# ProPrj_CraftVia-MakerCard-S-v1-Rev0_2026.net
KiCad netlist of a schematic drawn in EasyEDA Pro
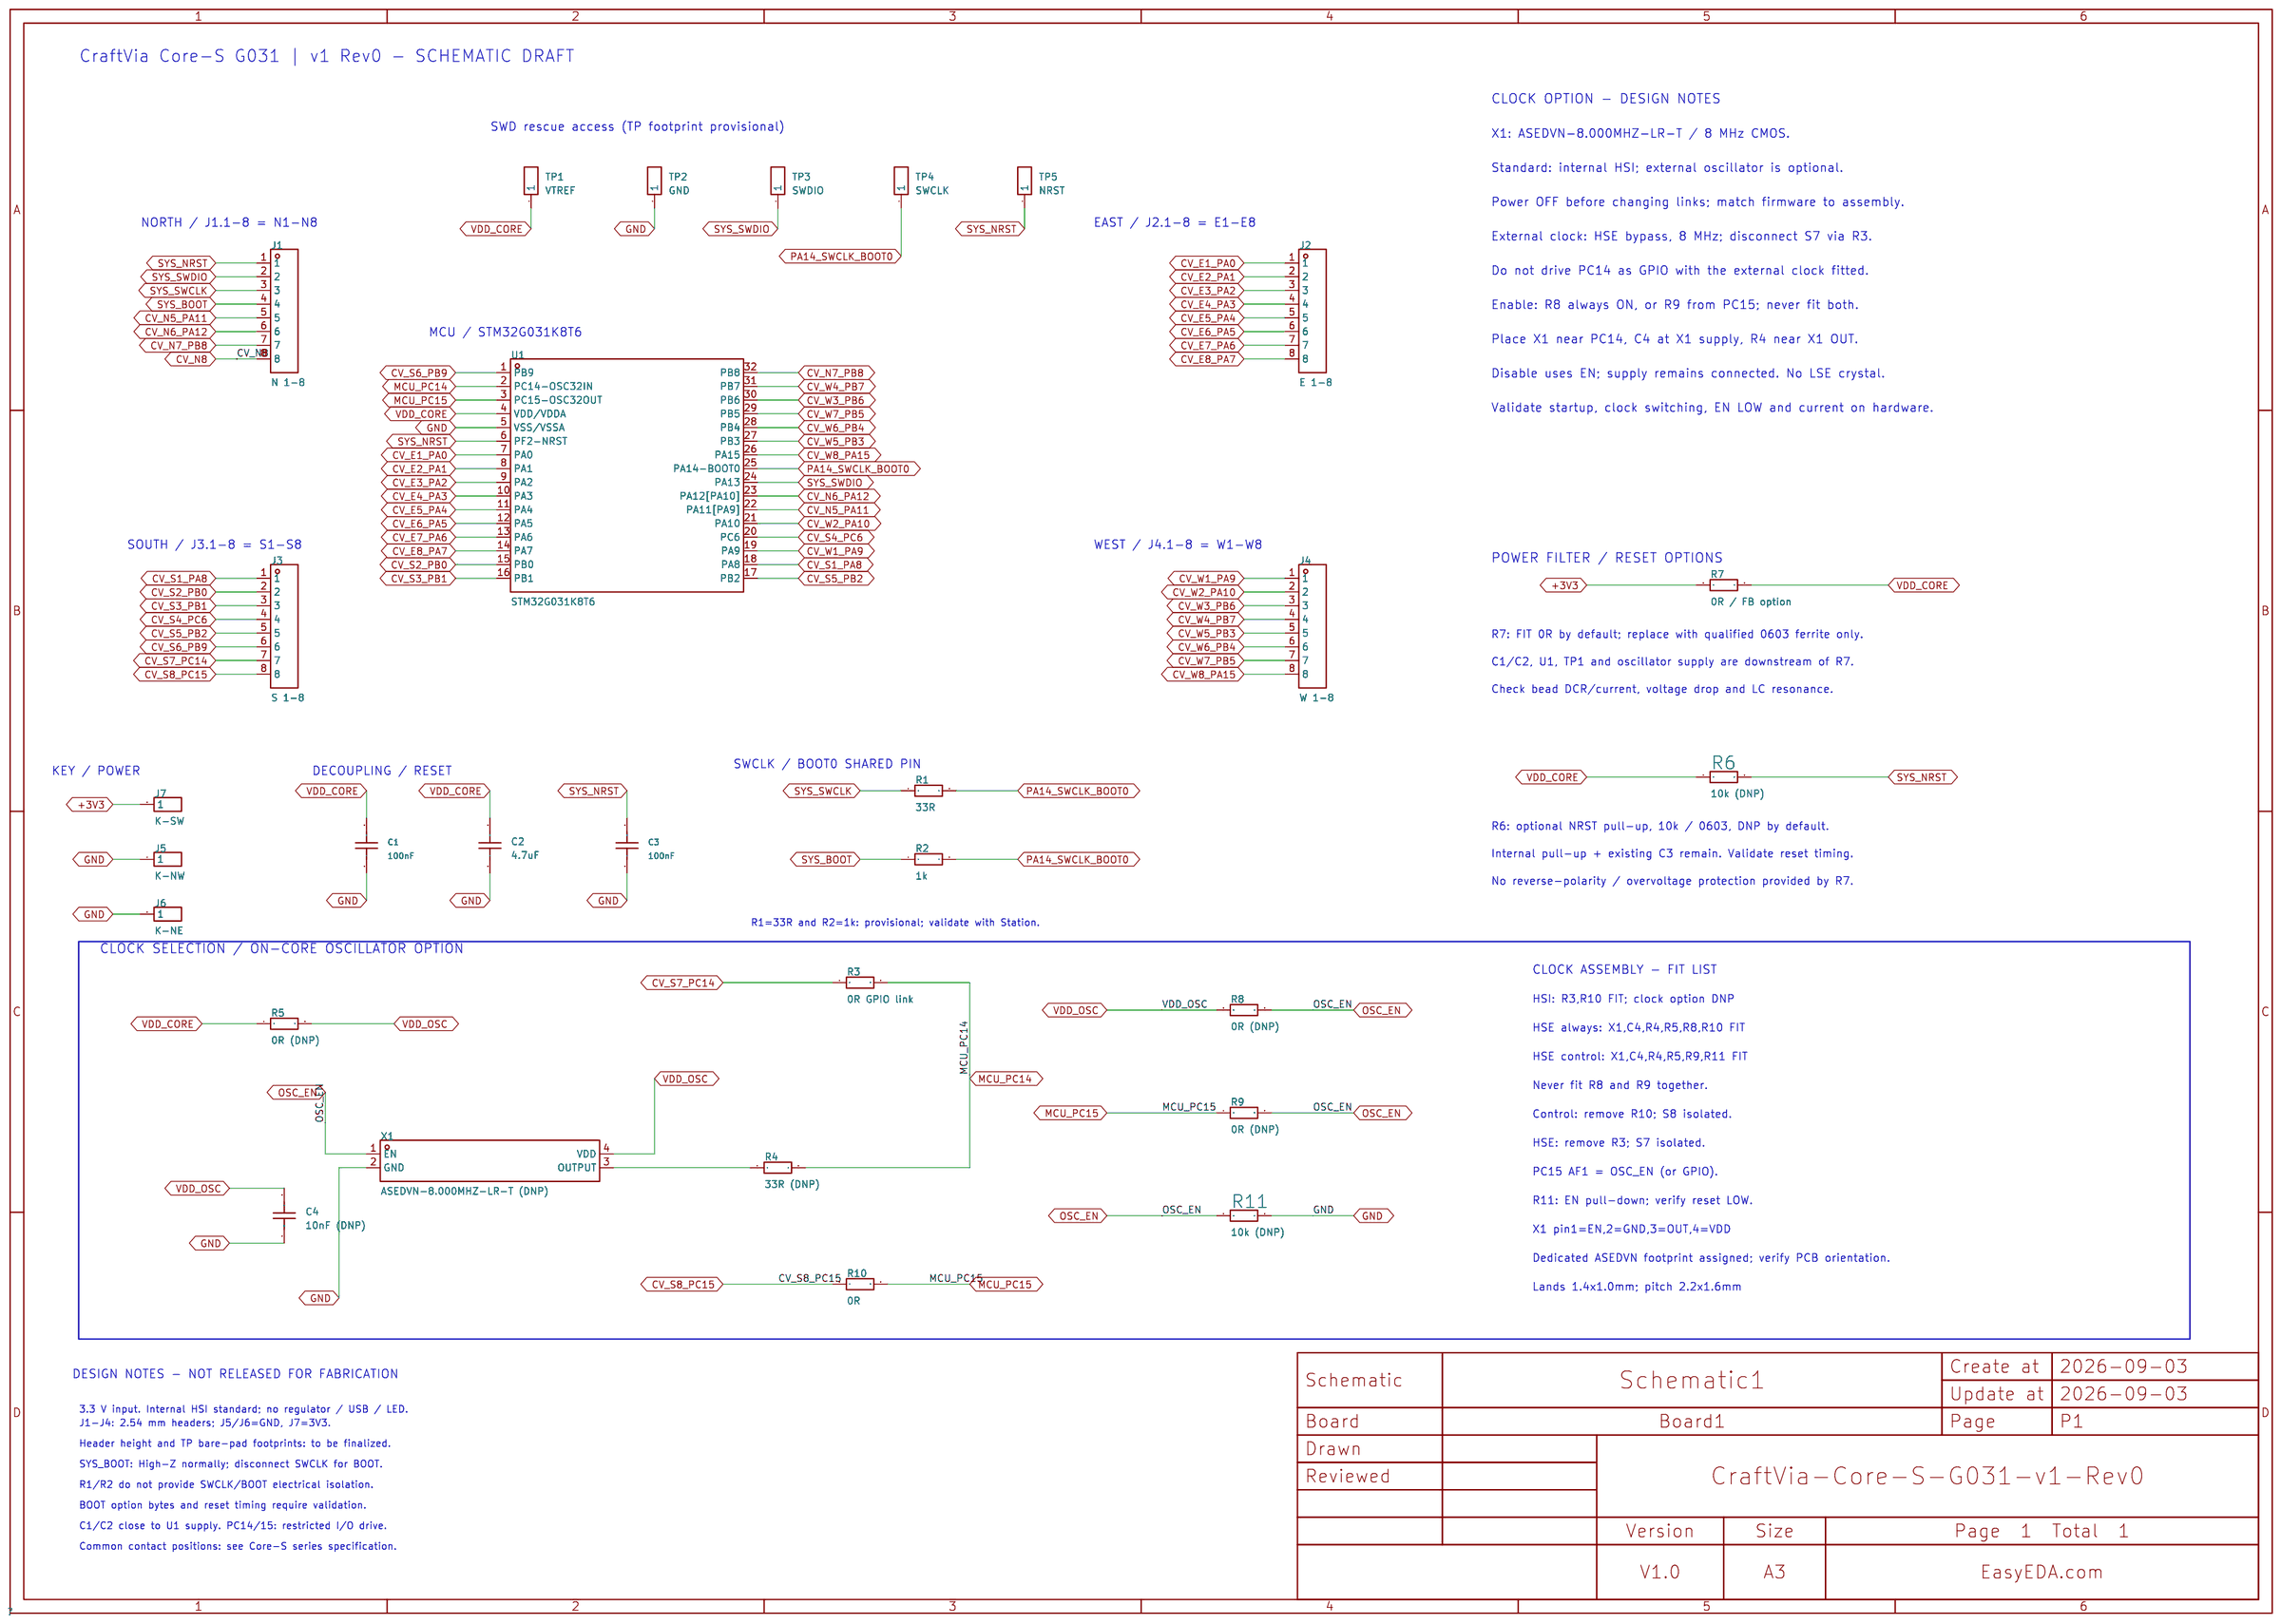
[diagram p0: Core-G031]
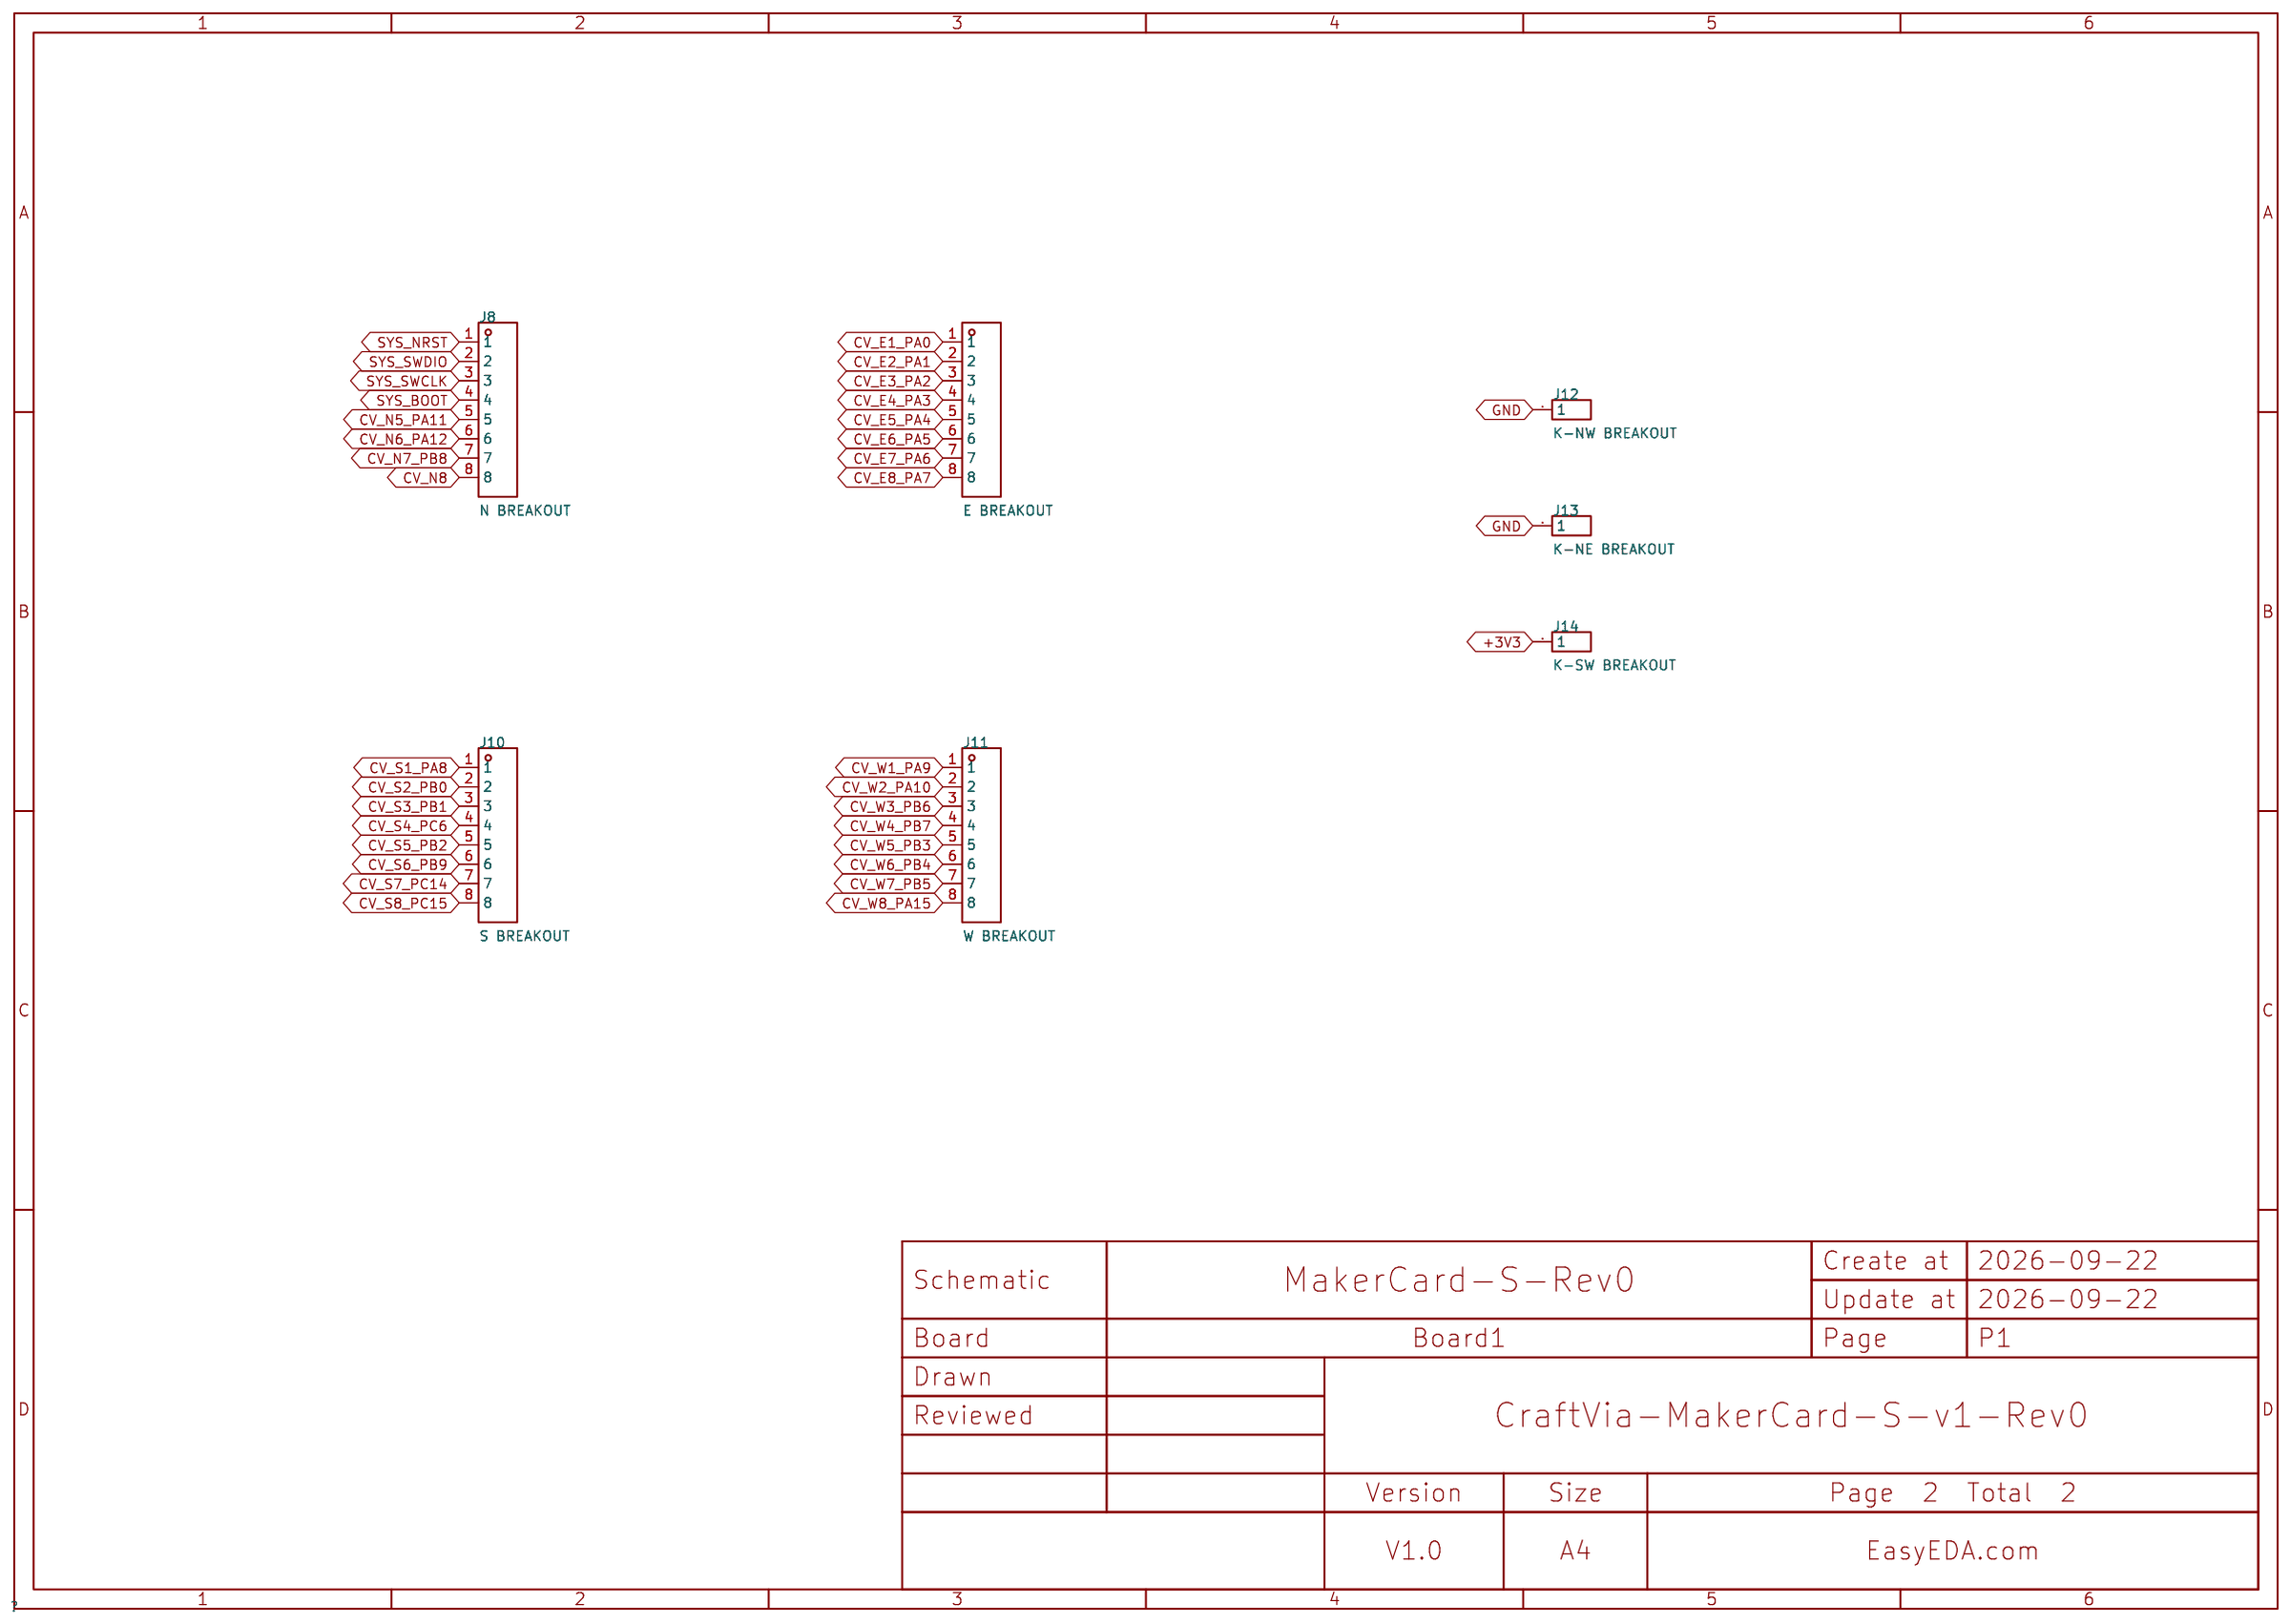
[diagram p1: 02_CORE_BREAKOUT]
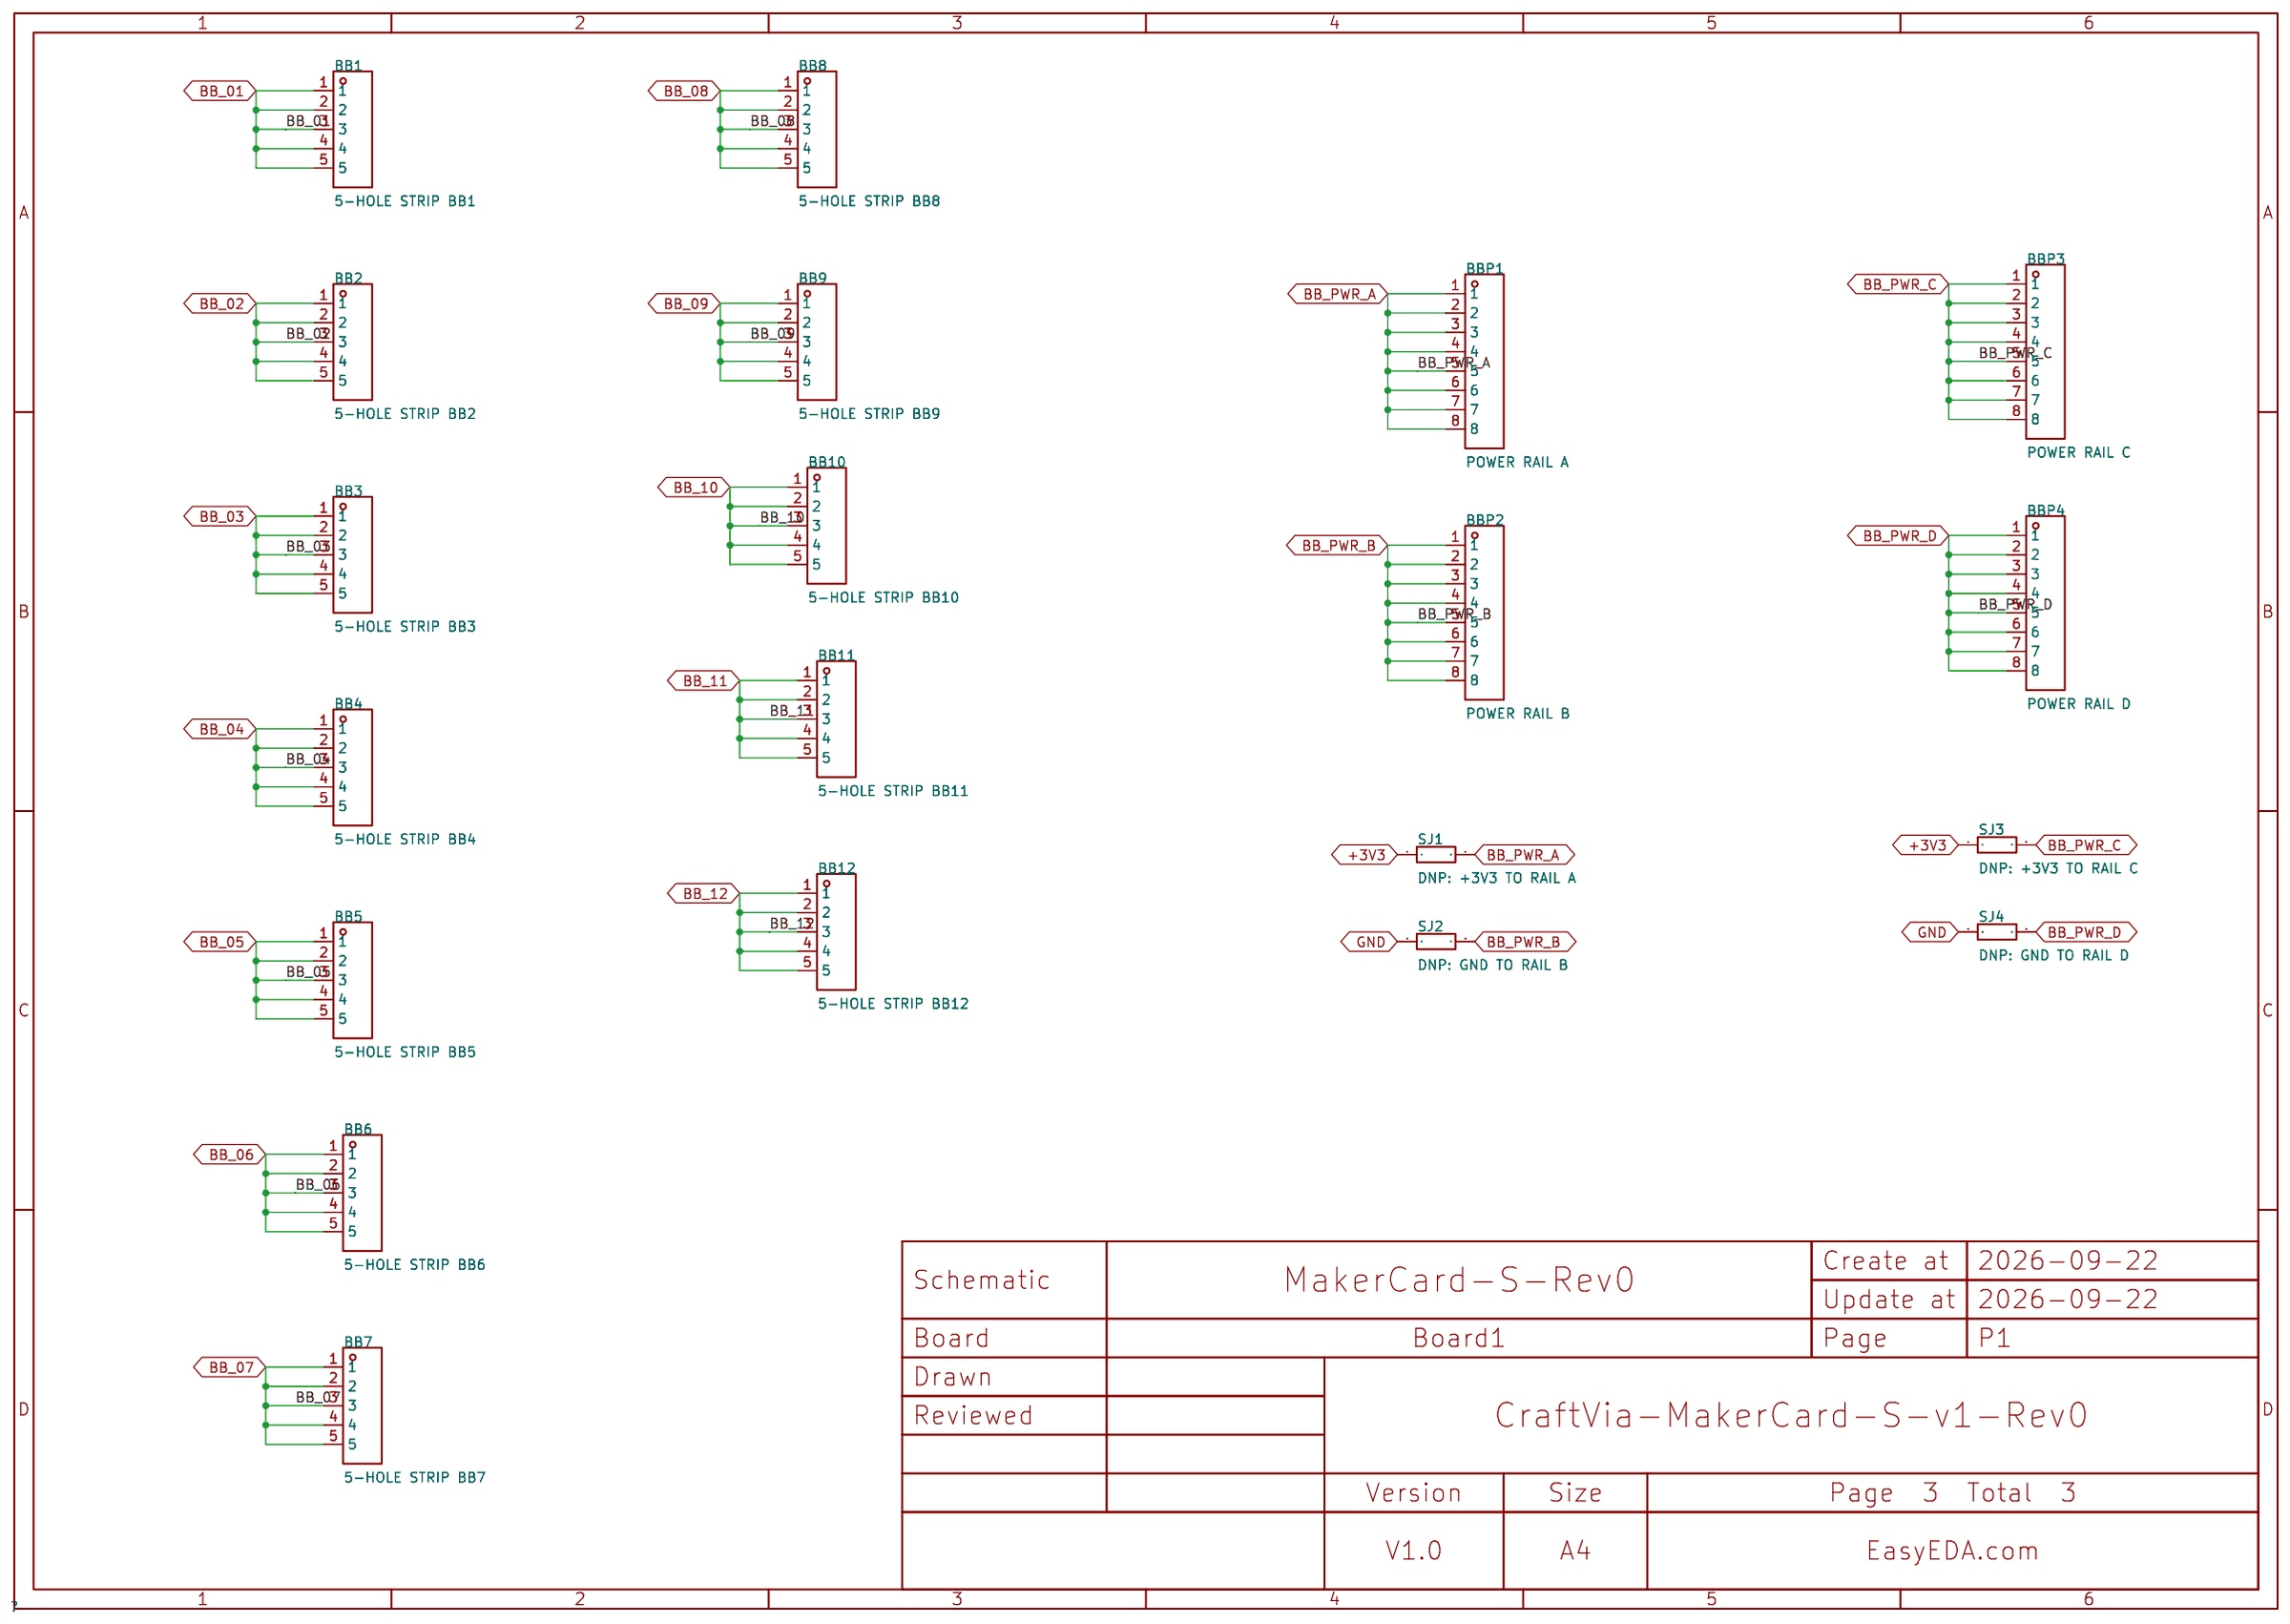
[diagram p2: 03_PROTO_AREA]

(export (version "E")
  (design (tool "Eeschema 10.0.6"))
  (components
    (comp (ref "C1")
      (value "100nF")
      (footprint "easyedapro:C0603")
      (description "Capacitance:100nF Tolerance:±10% Tolerance:±10% Voltage Rating:50V Temperature Coefficient:X7R")
      (fields
        (field (name "Manufacturer Part") "CC0603KRX7R9BB104")
        (field (name "Manufacturer") "YAGEO(国巨)")
      )
      (libsource (lib "easyedapro") (part "CC0603KRX7R9BB104"))
    )
    (comp (ref "C2")
      (value "4.7uF")
      (footprint "easyedapro:C0603")
      (description "Capacitance:4.7uF Tolerance:±10% Tolerance:±10% Voltage Rating:16V Temperature Coefficient:X5R")
      (fields
        (field (name "Manufacturer Part") "CL10A475KO8NNNC")
        (field (name "Manufacturer") "SAMSUNG(三星)")
      )
      (libsource (lib "easyedapro") (part "CL10A475KO8NNNC"))
    )
    (comp (ref "C3")
      (value "100nF")
      (footprint "easyedapro:C0603")
      (description "Capacitance:100nF Tolerance:±10% Tolerance:±10% Voltage Rating:50V Temperature Coefficient:X7R")
      (fields
        (field (name "Manufacturer Part") "CC0603KRX7R9BB104")
        (field (name "Manufacturer") "YAGEO(国巨)")
      )
      (libsource (lib "easyedapro") (part "CC0603KRX7R9BB104"))
    )
    (comp (ref "C4")
      (value "10nF (DNP)")
      (footprint "easyedapro:C0603")
      (description "Capacitance:10nF Tolerance:±10% Tolerance:±10% Voltage Rating:50V Temperature Coefficient:X7R")
      (fields (field (name "Manufacturer Part") "0603B103K500NT") (field (name "Manufacturer") "FH(风华)"))
      (libsource (lib "easyedapro") (part "0603B103K500NT"))
    )
    (comp (ref "J1")
      (value "N 1-8")
      (footprint "easyedapro:HDR-TH_8P-P2.54-V-M")
      (fields (field (name "Manufacturer Part") "直排针2.54mm 1*8P"))
      (libsource (lib "easyedapro") (part "Header2.54mm 1*8P"))
    )
    (comp (ref "J2")
      (value "E 1-8")
      (footprint "easyedapro:HDR-TH_8P-P2.54-V-M")
      (fields (field (name "Manufacturer Part") "直排针2.54mm 1*8P"))
      (libsource (lib "easyedapro") (part "Header2.54mm 1*8P"))
    )
    (comp (ref "J3")
      (value "S 1-8")
      (footprint "easyedapro:HDR-TH_8P-P2.54-V-M")
      (fields (field (name "Manufacturer Part") "直排针2.54mm 1*8P"))
      (libsource (lib "easyedapro") (part "Header2.54mm 1*8P"))
    )
    (comp (ref "J4")
      (value "W 1-8")
      (footprint "easyedapro:HDR-TH_8P-P2.54-V-M")
      (fields (field (name "Manufacturer Part") "直排针2.54mm 1*8P"))
      (libsource (lib "easyedapro") (part "Header2.54mm 1*8P"))
    )
    (comp (ref "J5")
      (value "K-NW")
      (footprint "easyedapro:HDR-TH_1P-P2.54-V-M")
      (fields (field (name "Manufacturer Part") "2.54-1*1P针") (field (name "Manufacturer") "BOOMELE(博穆精密)"))
      (libsource (lib "easyedapro") (part "Header-Male-2.54_1x1"))
    )
    (comp (ref "J6")
      (value "K-NE")
      (footprint "easyedapro:HDR-TH_1P-P2.54-V-M")
      (fields (field (name "Manufacturer Part") "2.54-1*1P针") (field (name "Manufacturer") "BOOMELE(博穆精密)"))
      (libsource (lib "easyedapro") (part "Header-Male-2.54_1x1"))
    )
    (comp (ref "J7")
      (value "K-SW")
      (footprint "easyedapro:HDR-TH_1P-P2.54-V-M")
      (fields (field (name "Manufacturer Part") "2.54-1*1P针") (field (name "Manufacturer") "BOOMELE(博穆精密)"))
      (libsource (lib "easyedapro") (part "Header-Male-2.54_1x1"))
    )
    (comp (ref "R1")
      (value "33Ω")
      (footprint "easyedapro:R0603")
      (fields
        (field (name "Manufacturer Part") "0603WAF330JT5E")
        (field (name "Manufacturer") "UNI-ROYAL(厚声)")
        (field (name "Tolerance") "±1%")
      )
      (libsource (lib "easyedapro") (part "0603WAF330JT5E"))
    )
    (comp (ref "R2")
      (value "1kΩ")
      (footprint "easyedapro:R0603")
      (fields
        (field (name "Manufacturer Part") "0603WAF1001T5E")
        (field (name "Manufacturer") "UNI-ROYAL(厚声)")
        (field (name "Tolerance") "±1%")
      )
      (libsource (lib "easyedapro") (part "0603WAF1001T5E"))
    )
    (comp (ref "R3")
      (value "0Ω")
      (footprint "easyedapro:R0603")
      (fields
        (field (name "Manufacturer Part") "0603WAF0000T5E")
        (field (name "Manufacturer") "UNI-ROYAL(厚声)")
        (field (name "Tolerance") "±1%")
      )
      (libsource (lib "easyedapro") (part "0603WAF0000T5E"))
    )
    (comp (ref "R4")
      (value "33Ω")
      (footprint "easyedapro:R0603")
      (fields
        (field (name "Manufacturer Part") "0603WAF330JT5E")
        (field (name "Manufacturer") "UNI-ROYAL(厚声)")
        (field (name "Tolerance") "±1%")
      )
      (libsource (lib "easyedapro") (part "0603WAF330JT5E"))
    )
    (comp (ref "R5")
      (value "0Ω")
      (footprint "easyedapro:R0603")
      (fields
        (field (name "Manufacturer Part") "0603WAF0000T5E")
        (field (name "Manufacturer") "UNI-ROYAL(厚声)")
        (field (name "Tolerance") "±1%")
      )
      (libsource (lib "easyedapro") (part "0603WAF0000T5E"))
    )
    (comp (ref "R6")
      (value "10kΩ")
      (footprint "easyedapro:R0603")
      (fields
        (field (name "Manufacturer Part") "0603WAF1002T5E")
        (field (name "Manufacturer") "UNI-ROYAL(厚声)")
        (field (name "Tolerance") "±1%")
      )
      (libsource (lib "easyedapro") (part "0603WAF1002T5E"))
    )
    (comp (ref "R7")
      (value "0Ω")
      (footprint "easyedapro:R0603")
      (fields
        (field (name "Manufacturer Part") "0603WAF0000T5E")
        (field (name "Manufacturer") "UNI-ROYAL(厚声)")
        (field (name "Tolerance") "±1%")
      )
      (libsource (lib "easyedapro") (part "0603WAF0000T5E"))
    )
    (comp (ref "R8")
      (value "0Ω")
      (footprint "easyedapro:R0603")
      (fields
        (field (name "Manufacturer Part") "0603WAF0000T5E")
        (field (name "Manufacturer") "UNI-ROYAL(厚声)")
        (field (name "Tolerance") "±1%")
      )
      (libsource (lib "easyedapro") (part "0603WAF0000T5E"))
    )
    (comp (ref "R9")
      (value "0Ω")
      (footprint "easyedapro:R0603")
      (fields
        (field (name "Manufacturer Part") "0603WAF0000T5E")
        (field (name "Manufacturer") "UNI-ROYAL(厚声)")
        (field (name "Tolerance") "±1%")
      )
      (libsource (lib "easyedapro") (part "0603WAF0000T5E"))
    )
    (comp (ref "R10")
      (value "0Ω")
      (footprint "easyedapro:R0603")
      (fields
        (field (name "Manufacturer Part") "0603WAF0000T5E")
        (field (name "Manufacturer") "UNI-ROYAL(厚声)")
        (field (name "Tolerance") "±1%")
      )
      (libsource (lib "easyedapro") (part "0603WAF0000T5E"))
    )
    (comp (ref "R11")
      (value "10kΩ")
      (footprint "easyedapro:R0603")
      (fields
        (field (name "Manufacturer Part") "0603WAF1002T5E")
        (field (name "Manufacturer") "UNI-ROYAL(厚声)")
        (field (name "Tolerance") "±1%")
      )
      (libsource (lib "easyedapro") (part "0603WAF1002T5E"))
    )
    (comp (ref "TP1")
      (value "VTREF")
      (footprint "easyedapro:HDR-TH_1P-P2.54-V-M")
      (fields (field (name "Manufacturer Part") "2.54-1*1P针") (field (name "Manufacturer") "BOOMELE(博穆精密)"))
      (libsource (lib "easyedapro") (part "Header-Male-2.54_1x1"))
    )
    (comp (ref "TP2")
      (value "GND")
      (footprint "easyedapro:HDR-TH_1P-P2.54-V-M")
      (fields (field (name "Manufacturer Part") "2.54-1*1P针") (field (name "Manufacturer") "BOOMELE(博穆精密)"))
      (libsource (lib "easyedapro") (part "Header-Male-2.54_1x1"))
    )
    (comp (ref "TP3")
      (value "SWDIO")
      (footprint "easyedapro:HDR-TH_1P-P2.54-V-M")
      (fields (field (name "Manufacturer Part") "2.54-1*1P针") (field (name "Manufacturer") "BOOMELE(博穆精密)"))
      (libsource (lib "easyedapro") (part "Header-Male-2.54_1x1"))
    )
    (comp (ref "TP4")
      (value "SWCLK")
      (footprint "easyedapro:HDR-TH_1P-P2.54-V-M")
      (fields (field (name "Manufacturer Part") "2.54-1*1P针") (field (name "Manufacturer") "BOOMELE(博穆精密)"))
      (libsource (lib "easyedapro") (part "Header-Male-2.54_1x1"))
    )
    (comp (ref "TP5")
      (value "NRST")
      (footprint "easyedapro:HDR-TH_1P-P2.54-V-M")
      (fields (field (name "Manufacturer Part") "2.54-1*1P针") (field (name "Manufacturer") "BOOMELE(博穆精密)"))
      (libsource (lib "easyedapro") (part "Header-Male-2.54_1x1"))
    )
    (comp (ref "U1")
      (value "STM32G031K8T6")
      (footprint "easyedapro:LQFP-32_L7.0-W7.0-P0.80-LS9.0-BL")
      (fields (field (name "Manufacturer") "ST(意法半导体)"))
      (libsource (lib "easyedapro") (part "STM32G031K8T6"))
    )
    (comp (ref "X1")
      (value "8MHz")
      (footprint "easyedapro:CraftVia_ASEDVN_3225_4P")
      (fields
        (field (name "Manufacturer Part") "ASEDVN-8.000MHZ-LR-T")
        (field (name "Manufacturer") "Abracon")
      )
      (libsource (lib "easyedapro") (part "ASEDVN-8.000MHZ-LR-T"))
    )
    (comp (ref "J8")
      (value "N BREAKOUT")
      (footprint "easyedapro:HDR-TH_8P-P2.54-V-M")
      (description "MakerCard-S external 2.54mm breakout; DNP")
      (fields (field (name "Manufacturer Part") "直排针2.54mm 1*8P"))
      (libsource (lib "easyedapro") (part "Header2.54mm 1*8P"))
    )
    (comp (ref "J9")
      (value "E BREAKOUT")
      (footprint "easyedapro:HDR-TH_8P-P2.54-V-M")
      (description "MakerCard-S external 2.54mm breakout; DNP")
      (fields (field (name "Manufacturer Part") "直排针2.54mm 1*8P"))
      (libsource (lib "easyedapro") (part "Header2.54mm 1*8P"))
    )
    (comp (ref "J10")
      (value "S BREAKOUT")
      (footprint "easyedapro:HDR-TH_8P-P2.54-V-M")
      (description "MakerCard-S external 2.54mm breakout; DNP")
      (fields (field (name "Manufacturer Part") "直排针2.54mm 1*8P"))
      (libsource (lib "easyedapro") (part "Header2.54mm 1*8P"))
    )
    (comp (ref "J11")
      (value "W BREAKOUT")
      (footprint "easyedapro:HDR-TH_8P-P2.54-V-M")
      (description "MakerCard-S external 2.54mm breakout; DNP")
      (fields (field (name "Manufacturer Part") "直排针2.54mm 1*8P"))
      (libsource (lib "easyedapro") (part "Header2.54mm 1*8P"))
    )
    (comp (ref "J12")
      (value "K-NW BREAKOUT")
      (footprint "easyedapro:HDR-TH_1P-P2.54-V-M")
      (description "MakerCard-S external 2.54mm breakout; DNP")
      (fields (field (name "Manufacturer Part") "2.54-1*1P针") (field (name "Manufacturer") "BOOMELE(博穆精密)"))
      (libsource (lib "easyedapro") (part "Header-Male-2.54_1x1"))
    )
    (comp (ref "J13")
      (value "K-NE BREAKOUT")
      (footprint "easyedapro:HDR-TH_1P-P2.54-V-M")
      (description "MakerCard-S external 2.54mm breakout; DNP")
      (fields (field (name "Manufacturer Part") "2.54-1*1P针") (field (name "Manufacturer") "BOOMELE(博穆精密)"))
      (libsource (lib "easyedapro") (part "Header-Male-2.54_1x1"))
    )
    (comp (ref "J14")
      (value "K-SW BREAKOUT")
      (footprint "easyedapro:HDR-TH_1P-P2.54-V-M")
      (description "MakerCard-S external 2.54mm breakout; DNP")
      (fields (field (name "Manufacturer Part") "2.54-1*1P针") (field (name "Manufacturer") "BOOMELE(博穆精密)"))
      (libsource (lib "easyedapro") (part "Header-Male-2.54_1x1"))
    )
    (comp (ref "BB1")
      (value "5-HOLE STRIP BB1")
      (footprint "easyedapro:HDR-TH_5P-P2.54-V-M")
      (description "MakerCard-S breadboard-style five-hole connected strip; DNP")
      (fields (field (name "Manufacturer Part") "2.54mm 1*5P 直排针"))
      (libsource (lib "easyedapro") (part "2.54mm 1*5P Header"))
    )
    (comp (ref "BB2")
      (value "5-HOLE STRIP BB2")
      (footprint "easyedapro:HDR-TH_5P-P2.54-V-M")
      (description "MakerCard-S breadboard-style five-hole connected strip; DNP")
      (fields (field (name "Manufacturer Part") "2.54mm 1*5P 直排针"))
      (libsource (lib "easyedapro") (part "2.54mm 1*5P Header"))
    )
    (comp (ref "BB3")
      (value "5-HOLE STRIP BB3")
      (footprint "easyedapro:HDR-TH_5P-P2.54-V-M")
      (description "MakerCard-S breadboard-style five-hole connected strip; DNP")
      (fields (field (name "Manufacturer Part") "2.54mm 1*5P 直排针"))
      (libsource (lib "easyedapro") (part "2.54mm 1*5P Header"))
    )
    (comp (ref "BB4")
      (value "5-HOLE STRIP BB4")
      (footprint "easyedapro:HDR-TH_5P-P2.54-V-M")
      (description "MakerCard-S breadboard-style five-hole connected strip; DNP")
      (fields (field (name "Manufacturer Part") "2.54mm 1*5P 直排针"))
      (libsource (lib "easyedapro") (part "2.54mm 1*5P Header"))
    )
    (comp (ref "BB5")
      (value "5-HOLE STRIP BB5")
      (footprint "easyedapro:HDR-TH_5P-P2.54-V-M")
      (description "MakerCard-S breadboard-style five-hole connected strip; DNP")
      (fields (field (name "Manufacturer Part") "2.54mm 1*5P 直排针"))
      (libsource (lib "easyedapro") (part "2.54mm 1*5P Header"))
    )
    (comp (ref "BB6")
      (value "5-HOLE STRIP BB6")
      (footprint "easyedapro:HDR-TH_5P-P2.54-V-M")
      (description "MakerCard-S breadboard-style five-hole connected strip; DNP")
      (fields (field (name "Manufacturer Part") "2.54mm 1*5P 直排针"))
      (libsource (lib "easyedapro") (part "2.54mm 1*5P Header"))
    )
    (comp (ref "BB7")
      (value "5-HOLE STRIP BB7")
      (footprint "easyedapro:HDR-TH_5P-P2.54-V-M")
      (description "MakerCard-S breadboard-style five-hole connected strip; DNP")
      (fields (field (name "Manufacturer Part") "2.54mm 1*5P 直排针"))
      (libsource (lib "easyedapro") (part "2.54mm 1*5P Header"))
    )
    (comp (ref "BB8")
      (value "5-HOLE STRIP BB8")
      (footprint "easyedapro:HDR-TH_5P-P2.54-V-M")
      (description "MakerCard-S breadboard-style five-hole connected strip; DNP")
      (fields (field (name "Manufacturer Part") "2.54mm 1*5P 直排针"))
      (libsource (lib "easyedapro") (part "2.54mm 1*5P Header"))
    )
    (comp (ref "BB9")
      (value "5-HOLE STRIP BB9")
      (footprint "easyedapro:HDR-TH_5P-P2.54-V-M")
      (description "MakerCard-S breadboard-style five-hole connected strip; DNP")
      (fields (field (name "Manufacturer Part") "2.54mm 1*5P 直排针"))
      (libsource (lib "easyedapro") (part "2.54mm 1*5P Header"))
    )
    (comp (ref "BB10")
      (value "5-HOLE STRIP BB10")
      (footprint "easyedapro:HDR-TH_5P-P2.54-V-M")
      (description "MakerCard-S breadboard-style five-hole connected strip; DNP")
      (fields (field (name "Manufacturer Part") "2.54mm 1*5P 直排针"))
      (libsource (lib "easyedapro") (part "2.54mm 1*5P Header"))
    )
    (comp (ref "BB11")
      (value "5-HOLE STRIP BB11")
      (footprint "easyedapro:HDR-TH_5P-P2.54-V-M")
      (description "MakerCard-S breadboard-style five-hole connected strip; DNP")
      (fields (field (name "Manufacturer Part") "2.54mm 1*5P 直排针"))
      (libsource (lib "easyedapro") (part "2.54mm 1*5P Header"))
    )
    (comp (ref "BB12")
      (value "5-HOLE STRIP BB12")
      (footprint "easyedapro:HDR-TH_5P-P2.54-V-M")
      (description "MakerCard-S breadboard-style five-hole connected strip; DNP")
      (fields (field (name "Manufacturer Part") "2.54mm 1*5P 直排针"))
      (libsource (lib "easyedapro") (part "2.54mm 1*5P Header"))
    )
    (comp (ref "BBP1")
      (value "POWER RAIL A")
      (footprint "easyedapro:HDR-TH_8P-P2.54-V-M")
      (description "MakerCard-S configurable eight-hole breadboard power rail; DNP")
      (fields (field (name "Manufacturer Part") "直排针2.54mm 1*8P"))
      (libsource (lib "easyedapro") (part "Header2.54mm 1*8P"))
    )
    (comp (ref "BBP2")
      (value "POWER RAIL B")
      (footprint "easyedapro:HDR-TH_8P-P2.54-V-M")
      (description "MakerCard-S configurable eight-hole breadboard power rail; DNP")
      (fields (field (name "Manufacturer Part") "直排针2.54mm 1*8P"))
      (libsource (lib "easyedapro") (part "Header2.54mm 1*8P"))
    )
    (comp (ref "BBP3")
      (value "POWER RAIL C")
      (footprint "easyedapro:HDR-TH_8P-P2.54-V-M")
      (description "MakerCard-S configurable eight-hole breadboard power rail; DNP")
      (fields (field (name "Manufacturer Part") "直排针2.54mm 1*8P"))
      (libsource (lib "easyedapro") (part "Header2.54mm 1*8P"))
    )
    (comp (ref "BBP4")
      (value "POWER RAIL D")
      (footprint "easyedapro:HDR-TH_8P-P2.54-V-M")
      (description "MakerCard-S configurable eight-hole breadboard power rail; DNP")
      (fields (field (name "Manufacturer Part") "直排针2.54mm 1*8P"))
      (libsource (lib "easyedapro") (part "Header2.54mm 1*8P"))
    )
    (comp (ref "SJ1")
      (value "0Ω")
      (footprint "easyedapro:R0603")
      (description "Optional 0603 solder bridge / 0R link; DNP")
      (fields
        (field (name "Manufacturer Part") "0603WAF0000T5E")
        (field (name "Manufacturer") "UNI-ROYAL(厚声)")
      )
      (libsource (lib "easyedapro") (part "0603WAF0000T5E"))
    )
    (comp (ref "SJ2")
      (value "0Ω")
      (footprint "easyedapro:R0603")
      (description "Optional 0603 solder bridge / 0R link; DNP")
      (fields
        (field (name "Manufacturer Part") "0603WAF0000T5E")
        (field (name "Manufacturer") "UNI-ROYAL(厚声)")
      )
      (libsource (lib "easyedapro") (part "0603WAF0000T5E"))
    )
    (comp (ref "SJ3")
      (value "0Ω")
      (footprint "easyedapro:R0603")
      (description "Optional 0603 solder bridge / 0R link; DNP")
      (fields
        (field (name "Manufacturer Part") "0603WAF0000T5E")
        (field (name "Manufacturer") "UNI-ROYAL(厚声)")
      )
      (libsource (lib "easyedapro") (part "0603WAF0000T5E"))
    )
    (comp (ref "SJ4")
      (value "0Ω")
      (footprint "easyedapro:R0603")
      (description "Optional 0603 solder bridge / 0R link; DNP")
      (fields
        (field (name "Manufacturer Part") "0603WAF0000T5E")
        (field (name "Manufacturer") "UNI-ROYAL(厚声)")
      )
      (libsource (lib "easyedapro") (part "0603WAF0000T5E"))
    )
  )
  (nets
    (net (code "1") (name "+3V3") (class "Default")
      (node (ref "J14") (pin "1") (pinfunction "1_1") (pintype "input"))
      (node (ref "J7") (pin "1") (pinfunction "1_1") (pintype "input"))
      (node (ref "R7") (pin "1") (pinfunction "1_1") (pintype "input"))
      (node (ref "SJ1") (pin "1") (pinfunction "1_1") (pintype "input"))
      (node (ref "SJ3") (pin "1") (pinfunction "1_1") (pintype "input"))
    )
    (net (code "2") (name "BB_01") (class "Default")
      (node (ref "BB1") (pin "1") (pinfunction "1_1") (pintype "unspecified"))
      (node (ref "BB1") (pin "2") (pinfunction "2_2") (pintype "unspecified"))
      (node (ref "BB1") (pin "3") (pinfunction "3_3") (pintype "unspecified"))
      (node (ref "BB1") (pin "4") (pinfunction "4_4") (pintype "unspecified"))
      (node (ref "BB1") (pin "5") (pinfunction "5_5") (pintype "unspecified"))
    )
    (net (code "3") (name "BB_02") (class "Default")
      (node (ref "BB2") (pin "1") (pinfunction "1_1") (pintype "unspecified"))
      (node (ref "BB2") (pin "2") (pinfunction "2_2") (pintype "unspecified"))
      (node (ref "BB2") (pin "3") (pinfunction "3_3") (pintype "unspecified"))
      (node (ref "BB2") (pin "4") (pinfunction "4_4") (pintype "unspecified"))
      (node (ref "BB2") (pin "5") (pinfunction "5_5") (pintype "unspecified"))
    )
    (net (code "4") (name "BB_03") (class "Default")
      (node (ref "BB3") (pin "1") (pinfunction "1_1") (pintype "unspecified"))
      (node (ref "BB3") (pin "2") (pinfunction "2_2") (pintype "unspecified"))
      (node (ref "BB3") (pin "3") (pinfunction "3_3") (pintype "unspecified"))
      (node (ref "BB3") (pin "4") (pinfunction "4_4") (pintype "unspecified"))
      (node (ref "BB3") (pin "5") (pinfunction "5_5") (pintype "unspecified"))
    )
    (net (code "5") (name "BB_04") (class "Default")
      (node (ref "BB4") (pin "1") (pinfunction "1_1") (pintype "unspecified"))
      (node (ref "BB4") (pin "2") (pinfunction "2_2") (pintype "unspecified"))
      (node (ref "BB4") (pin "3") (pinfunction "3_3") (pintype "unspecified"))
      (node (ref "BB4") (pin "4") (pinfunction "4_4") (pintype "unspecified"))
      (node (ref "BB4") (pin "5") (pinfunction "5_5") (pintype "unspecified"))
    )
    (net (code "6") (name "BB_05") (class "Default")
      (node (ref "BB5") (pin "1") (pinfunction "1_1") (pintype "unspecified"))
      (node (ref "BB5") (pin "2") (pinfunction "2_2") (pintype "unspecified"))
      (node (ref "BB5") (pin "3") (pinfunction "3_3") (pintype "unspecified"))
      (node (ref "BB5") (pin "4") (pinfunction "4_4") (pintype "unspecified"))
      (node (ref "BB5") (pin "5") (pinfunction "5_5") (pintype "unspecified"))
    )
    (net (code "7") (name "BB_06") (class "Default")
      (node (ref "BB6") (pin "1") (pinfunction "1_1") (pintype "unspecified"))
      (node (ref "BB6") (pin "2") (pinfunction "2_2") (pintype "unspecified"))
      (node (ref "BB6") (pin "3") (pinfunction "3_3") (pintype "unspecified"))
      (node (ref "BB6") (pin "4") (pinfunction "4_4") (pintype "unspecified"))
      (node (ref "BB6") (pin "5") (pinfunction "5_5") (pintype "unspecified"))
    )
    (net (code "8") (name "BB_07") (class "Default")
      (node (ref "BB7") (pin "1") (pinfunction "1_1") (pintype "unspecified"))
      (node (ref "BB7") (pin "2") (pinfunction "2_2") (pintype "unspecified"))
      (node (ref "BB7") (pin "3") (pinfunction "3_3") (pintype "unspecified"))
      (node (ref "BB7") (pin "4") (pinfunction "4_4") (pintype "unspecified"))
      (node (ref "BB7") (pin "5") (pinfunction "5_5") (pintype "unspecified"))
    )
    (net (code "9") (name "BB_08") (class "Default")
      (node (ref "BB8") (pin "1") (pinfunction "1_1") (pintype "unspecified"))
      (node (ref "BB8") (pin "2") (pinfunction "2_2") (pintype "unspecified"))
      (node (ref "BB8") (pin "3") (pinfunction "3_3") (pintype "unspecified"))
      (node (ref "BB8") (pin "4") (pinfunction "4_4") (pintype "unspecified"))
      (node (ref "BB8") (pin "5") (pinfunction "5_5") (pintype "unspecified"))
    )
    (net (code "10") (name "BB_09") (class "Default")
      (node (ref "BB9") (pin "1") (pinfunction "1_1") (pintype "unspecified"))
      (node (ref "BB9") (pin "2") (pinfunction "2_2") (pintype "unspecified"))
      (node (ref "BB9") (pin "3") (pinfunction "3_3") (pintype "unspecified"))
      (node (ref "BB9") (pin "4") (pinfunction "4_4") (pintype "unspecified"))
      (node (ref "BB9") (pin "5") (pinfunction "5_5") (pintype "unspecified"))
    )
    (net (code "11") (name "BB_10") (class "Default")
      (node (ref "BB10") (pin "1") (pinfunction "1_1") (pintype "unspecified"))
      (node (ref "BB10") (pin "2") (pinfunction "2_2") (pintype "unspecified"))
      (node (ref "BB10") (pin "3") (pinfunction "3_3") (pintype "unspecified"))
      (node (ref "BB10") (pin "4") (pinfunction "4_4") (pintype "unspecified"))
      (node (ref "BB10") (pin "5") (pinfunction "5_5") (pintype "unspecified"))
    )
    (net (code "12") (name "BB_11") (class "Default")
      (node (ref "BB11") (pin "1") (pinfunction "1_1") (pintype "unspecified"))
      (node (ref "BB11") (pin "2") (pinfunction "2_2") (pintype "unspecified"))
      (node (ref "BB11") (pin "3") (pinfunction "3_3") (pintype "unspecified"))
      (node (ref "BB11") (pin "4") (pinfunction "4_4") (pintype "unspecified"))
      (node (ref "BB11") (pin "5") (pinfunction "5_5") (pintype "unspecified"))
    )
    (net (code "13") (name "BB_12") (class "Default")
      (node (ref "BB12") (pin "1") (pinfunction "1_1") (pintype "unspecified"))
      (node (ref "BB12") (pin "2") (pinfunction "2_2") (pintype "unspecified"))
      (node (ref "BB12") (pin "3") (pinfunction "3_3") (pintype "unspecified"))
      (node (ref "BB12") (pin "4") (pinfunction "4_4") (pintype "unspecified"))
      (node (ref "BB12") (pin "5") (pinfunction "5_5") (pintype "unspecified"))
    )
    (net (code "14") (name "BB_PWR_A") (class "Default")
      (node (ref "BBP1") (pin "1") (pinfunction "1_1") (pintype "unspecified"))
      (node (ref "BBP1") (pin "2") (pinfunction "2_2") (pintype "unspecified"))
      (node (ref "BBP1") (pin "3") (pinfunction "3_3") (pintype "unspecified"))
      (node (ref "BBP1") (pin "4") (pinfunction "4_4") (pintype "unspecified"))
      (node (ref "BBP1") (pin "5") (pinfunction "5_5") (pintype "unspecified"))
      (node (ref "BBP1") (pin "6") (pinfunction "6_6") (pintype "unspecified"))
      (node (ref "BBP1") (pin "7") (pinfunction "7_7") (pintype "unspecified"))
      (node (ref "BBP1") (pin "8") (pinfunction "8_8") (pintype "unspecified"))
      (node (ref "SJ1") (pin "2") (pinfunction "2_2") (pintype "input"))
    )
    (net (code "15") (name "BB_PWR_B") (class "Default")
      (node (ref "BBP2") (pin "1") (pinfunction "1_1") (pintype "unspecified"))
      (node (ref "BBP2") (pin "2") (pinfunction "2_2") (pintype "unspecified"))
      (node (ref "BBP2") (pin "3") (pinfunction "3_3") (pintype "unspecified"))
      (node (ref "BBP2") (pin "4") (pinfunction "4_4") (pintype "unspecified"))
      (node (ref "BBP2") (pin "5") (pinfunction "5_5") (pintype "unspecified"))
      (node (ref "BBP2") (pin "6") (pinfunction "6_6") (pintype "unspecified"))
      (node (ref "BBP2") (pin "7") (pinfunction "7_7") (pintype "unspecified"))
      (node (ref "BBP2") (pin "8") (pinfunction "8_8") (pintype "unspecified"))
      (node (ref "SJ2") (pin "2") (pinfunction "2_2") (pintype "input"))
    )
    (net (code "16") (name "BB_PWR_C") (class "Default")
      (node (ref "BBP3") (pin "1") (pinfunction "1_1") (pintype "unspecified"))
      (node (ref "BBP3") (pin "2") (pinfunction "2_2") (pintype "unspecified"))
      (node (ref "BBP3") (pin "3") (pinfunction "3_3") (pintype "unspecified"))
      (node (ref "BBP3") (pin "4") (pinfunction "4_4") (pintype "unspecified"))
      (node (ref "BBP3") (pin "5") (pinfunction "5_5") (pintype "unspecified"))
      (node (ref "BBP3") (pin "6") (pinfunction "6_6") (pintype "unspecified"))
      (node (ref "BBP3") (pin "7") (pinfunction "7_7") (pintype "unspecified"))
      (node (ref "BBP3") (pin "8") (pinfunction "8_8") (pintype "unspecified"))
      (node (ref "SJ3") (pin "2") (pinfunction "2_2") (pintype "input"))
    )
    (net (code "17") (name "BB_PWR_D") (class "Default")
      (node (ref "BBP4") (pin "1") (pinfunction "1_1") (pintype "unspecified"))
      (node (ref "BBP4") (pin "2") (pinfunction "2_2") (pintype "unspecified"))
      (node (ref "BBP4") (pin "3") (pinfunction "3_3") (pintype "unspecified"))
      (node (ref "BBP4") (pin "4") (pinfunction "4_4") (pintype "unspecified"))
      (node (ref "BBP4") (pin "5") (pinfunction "5_5") (pintype "unspecified"))
      (node (ref "BBP4") (pin "6") (pinfunction "6_6") (pintype "unspecified"))
      (node (ref "BBP4") (pin "7") (pinfunction "7_7") (pintype "unspecified"))
      (node (ref "BBP4") (pin "8") (pinfunction "8_8") (pintype "unspecified"))
      (node (ref "SJ4") (pin "2") (pinfunction "2_2") (pintype "input"))
    )
    (net (code "18") (name "CV_E1_PA0") (class "Default")
      (node (ref "J2") (pin "1") (pinfunction "1_1") (pintype "unspecified"))
      (node (ref "J9") (pin "1") (pinfunction "1_1") (pintype "unspecified"))
      (node (ref "U1") (pin "7") (pinfunction "PA0_7") (pintype "unspecified"))
    )
    (net (code "19") (name "CV_E2_PA1") (class "Default")
      (node (ref "J2") (pin "2") (pinfunction "2_2") (pintype "unspecified"))
      (node (ref "J9") (pin "2") (pinfunction "2_2") (pintype "unspecified"))
      (node (ref "U1") (pin "8") (pinfunction "PA1_8") (pintype "unspecified"))
    )
    (net (code "20") (name "CV_E3_PA2") (class "Default")
      (node (ref "J2") (pin "3") (pinfunction "3_3") (pintype "unspecified"))
      (node (ref "J9") (pin "3") (pinfunction "3_3") (pintype "unspecified"))
      (node (ref "U1") (pin "9") (pinfunction "PA2_9") (pintype "unspecified"))
    )
    (net (code "21") (name "CV_E4_PA3") (class "Default")
      (node (ref "J2") (pin "4") (pinfunction "4_4") (pintype "unspecified"))
      (node (ref "J9") (pin "4") (pinfunction "4_4") (pintype "unspecified"))
      (node (ref "U1") (pin "10") (pinfunction "PA3_10") (pintype "unspecified"))
    )
    (net (code "22") (name "CV_E5_PA4") (class "Default")
      (node (ref "J2") (pin "5") (pinfunction "5_5") (pintype "unspecified"))
      (node (ref "J9") (pin "5") (pinfunction "5_5") (pintype "unspecified"))
      (node (ref "U1") (pin "11") (pinfunction "PA4_11") (pintype "unspecified"))
    )
    (net (code "23") (name "CV_E6_PA5") (class "Default")
      (node (ref "J2") (pin "6") (pinfunction "6_6") (pintype "unspecified"))
      (node (ref "J9") (pin "6") (pinfunction "6_6") (pintype "unspecified"))
      (node (ref "U1") (pin "12") (pinfunction "PA5_12") (pintype "unspecified"))
    )
    (net (code "24") (name "CV_E7_PA6") (class "Default")
      (node (ref "J2") (pin "7") (pinfunction "7_7") (pintype "unspecified"))
      (node (ref "J9") (pin "7") (pinfunction "7_7") (pintype "unspecified"))
      (node (ref "U1") (pin "13") (pinfunction "PA6_13") (pintype "unspecified"))
    )
    (net (code "25") (name "CV_E8_PA7") (class "Default")
      (node (ref "J2") (pin "8") (pinfunction "8_8") (pintype "unspecified"))
      (node (ref "J9") (pin "8") (pinfunction "8_8") (pintype "unspecified"))
      (node (ref "U1") (pin "14") (pinfunction "PA7_14") (pintype "unspecified"))
    )
    (net (code "26") (name "CV_N5_PA11") (class "Default")
      (node (ref "J1") (pin "5") (pinfunction "5_5") (pintype "unspecified"))
      (node (ref "J8") (pin "5") (pinfunction "5_5") (pintype "unspecified"))
      (node (ref "U1") (pin "22") (pinfunction "PA11[PA9]_22") (pintype "unspecified"))
    )
    (net (code "27") (name "CV_N6_PA12") (class "Default")
      (node (ref "J1") (pin "6") (pinfunction "6_6") (pintype "unspecified"))
      (node (ref "J8") (pin "6") (pinfunction "6_6") (pintype "unspecified"))
      (node (ref "U1") (pin "23") (pinfunction "PA12[PA10]_23") (pintype "unspecified"))
    )
    (net (code "28") (name "CV_N7_PB8") (class "Default")
      (node (ref "J1") (pin "7") (pinfunction "7_7") (pintype "unspecified"))
      (node (ref "J8") (pin "7") (pinfunction "7_7") (pintype "unspecified"))
      (node (ref "U1") (pin "32") (pinfunction "PB8_32") (pintype "unspecified"))
    )
    (net (code "29") (name "CV_N8") (class "Default")
      (node (ref "J1") (pin "8") (pinfunction "8_8") (pintype "unspecified"))
      (node (ref "J8") (pin "8") (pinfunction "8_8") (pintype "unspecified"))
    )
    (net (code "30") (name "CV_S1_PA8") (class "Default")
      (node (ref "J10") (pin "1") (pinfunction "1_1") (pintype "unspecified"))
      (node (ref "J3") (pin "1") (pinfunction "1_1") (pintype "unspecified"))
      (node (ref "U1") (pin "18") (pinfunction "PA8_18") (pintype "unspecified"))
    )
    (net (code "31") (name "CV_S2_PB0") (class "Default")
      (node (ref "J10") (pin "2") (pinfunction "2_2") (pintype "unspecified"))
      (node (ref "J3") (pin "2") (pinfunction "2_2") (pintype "unspecified"))
      (node (ref "U1") (pin "15") (pinfunction "PB0_15") (pintype "unspecified"))
    )
    (net (code "32") (name "CV_S3_PB1") (class "Default")
      (node (ref "J10") (pin "3") (pinfunction "3_3") (pintype "unspecified"))
      (node (ref "J3") (pin "3") (pinfunction "3_3") (pintype "unspecified"))
      (node (ref "U1") (pin "16") (pinfunction "PB1_16") (pintype "unspecified"))
    )
    (net (code "33") (name "CV_S4_PC6") (class "Default")
      (node (ref "J10") (pin "4") (pinfunction "4_4") (pintype "unspecified"))
      (node (ref "J3") (pin "4") (pinfunction "4_4") (pintype "unspecified"))
      (node (ref "U1") (pin "20") (pinfunction "PC6_20") (pintype "unspecified"))
    )
    (net (code "34") (name "CV_S5_PB2") (class "Default")
      (node (ref "J10") (pin "5") (pinfunction "5_5") (pintype "unspecified"))
      (node (ref "J3") (pin "5") (pinfunction "5_5") (pintype "unspecified"))
      (node (ref "U1") (pin "17") (pinfunction "PB2_17") (pintype "unspecified"))
    )
    (net (code "35") (name "CV_S6_PB9") (class "Default")
      (node (ref "J10") (pin "6") (pinfunction "6_6") (pintype "unspecified"))
      (node (ref "J3") (pin "6") (pinfunction "6_6") (pintype "unspecified"))
      (node (ref "U1") (pin "1") (pinfunction "PB9_1") (pintype "unspecified"))
    )
    (net (code "36") (name "CV_S7_PC14") (class "Default")
      (node (ref "J10") (pin "7") (pinfunction "7_7") (pintype "unspecified"))
      (node (ref "J3") (pin "7") (pinfunction "7_7") (pintype "unspecified"))
      (node (ref "R3") (pin "1") (pinfunction "1_1") (pintype "input"))
    )
    (net (code "37") (name "CV_S8_PC15") (class "Default")
      (node (ref "J10") (pin "8") (pinfunction "8_8") (pintype "unspecified"))
      (node (ref "J3") (pin "8") (pinfunction "8_8") (pintype "unspecified"))
      (node (ref "R10") (pin "1") (pinfunction "1_1") (pintype "input"))
    )
    (net (code "38") (name "CV_W1_PA9") (class "Default")
      (node (ref "J11") (pin "1") (pinfunction "1_1") (pintype "unspecified"))
      (node (ref "J4") (pin "1") (pinfunction "1_1") (pintype "unspecified"))
      (node (ref "U1") (pin "19") (pinfunction "PA9_19") (pintype "unspecified"))
    )
    (net (code "39") (name "CV_W2_PA10") (class "Default")
      (node (ref "J11") (pin "2") (pinfunction "2_2") (pintype "unspecified"))
      (node (ref "J4") (pin "2") (pinfunction "2_2") (pintype "unspecified"))
      (node (ref "U1") (pin "21") (pinfunction "PA10_21") (pintype "unspecified"))
    )
    (net (code "40") (name "CV_W3_PB6") (class "Default")
      (node (ref "J11") (pin "3") (pinfunction "3_3") (pintype "unspecified"))
      (node (ref "J4") (pin "3") (pinfunction "3_3") (pintype "unspecified"))
      (node (ref "U1") (pin "30") (pinfunction "PB6_30") (pintype "unspecified"))
    )
    (net (code "41") (name "CV_W4_PB7") (class "Default")
      (node (ref "J11") (pin "4") (pinfunction "4_4") (pintype "unspecified"))
      (node (ref "J4") (pin "4") (pinfunction "4_4") (pintype "unspecified"))
      (node (ref "U1") (pin "31") (pinfunction "PB7_31") (pintype "unspecified"))
    )
    (net (code "42") (name "CV_W5_PB3") (class "Default")
      (node (ref "J11") (pin "5") (pinfunction "5_5") (pintype "unspecified"))
      (node (ref "J4") (pin "5") (pinfunction "5_5") (pintype "unspecified"))
      (node (ref "U1") (pin "27") (pinfunction "PB3_27") (pintype "unspecified"))
    )
    (net (code "43") (name "CV_W6_PB4") (class "Default")
      (node (ref "J11") (pin "6") (pinfunction "6_6") (pintype "unspecified"))
      (node (ref "J4") (pin "6") (pinfunction "6_6") (pintype "unspecified"))
      (node (ref "U1") (pin "28") (pinfunction "PB4_28") (pintype "unspecified"))
    )
    (net (code "44") (name "CV_W7_PB5") (class "Default")
      (node (ref "J11") (pin "7") (pinfunction "7_7") (pintype "unspecified"))
      (node (ref "J4") (pin "7") (pinfunction "7_7") (pintype "unspecified"))
      (node (ref "U1") (pin "29") (pinfunction "PB5_29") (pintype "unspecified"))
    )
    (net (code "45") (name "CV_W8_PA15") (class "Default")
      (node (ref "J11") (pin "8") (pinfunction "8_8") (pintype "unspecified"))
      (node (ref "J4") (pin "8") (pinfunction "8_8") (pintype "unspecified"))
      (node (ref "U1") (pin "26") (pinfunction "PA15_26") (pintype "unspecified"))
    )
    (net (code "46") (name "GND") (class "Default")
      (node (ref "C1") (pin "1") (pinfunction "1_1") (pintype "unspecified"))
      (node (ref "C2") (pin "1") (pinfunction "1_1") (pintype "unspecified"))
      (node (ref "C3") (pin "1") (pinfunction "1_1") (pintype "unspecified"))
      (node (ref "C4") (pin "1") (pinfunction "1_1") (pintype "unspecified"))
      (node (ref "J12") (pin "1") (pinfunction "1_1") (pintype "input"))
      (node (ref "J13") (pin "1") (pinfunction "1_1") (pintype "input"))
      (node (ref "J5") (pin "1") (pinfunction "1_1") (pintype "input"))
      (node (ref "J6") (pin "1") (pinfunction "1_1") (pintype "input"))
      (node (ref "R11") (pin "2") (pinfunction "2_2") (pintype "input"))
      (node (ref "SJ2") (pin "1") (pinfunction "1_1") (pintype "input"))
      (node (ref "SJ4") (pin "1") (pinfunction "1_1") (pintype "input"))
      (node (ref "TP2") (pin "1") (pinfunction "1_1") (pintype "input"))
      (node (ref "U1") (pin "5") (pinfunction "VSS/VSSA_5") (pintype "unspecified"))
      (node (ref "X1") (pin "2") (pinfunction "GND_2") (pintype "unspecified"))
    )
    (net (code "47") (name "MCU_PC14") (class "Default")
      (node (ref "R3") (pin "2") (pinfunction "2_2") (pintype "input"))
      (node (ref "R4") (pin "2") (pinfunction "2_2") (pintype "input"))
      (node (ref "U1") (pin "2") (pinfunction "PC14-OSC32IN_2") (pintype "unspecified"))
    )
    (net (code "48") (name "MCU_PC15") (class "Default")
      (node (ref "R10") (pin "2") (pinfunction "2_2") (pintype "input"))
      (node (ref "R9") (pin "1") (pinfunction "1_1") (pintype "input"))
      (node (ref "U1") (pin "3") (pinfunction "PC15-OSC32OUT_3") (pintype "unspecified"))
    )
    (net (code "49") (name "Net-(X1-OUTPUT)") (class "Default")
      (node (ref "R4") (pin "1") (pinfunction "1_1") (pintype "input"))
      (node (ref "X1") (pin "3") (pinfunction "OUTPUT_3") (pintype "unspecified"))
    )
    (net (code "50") (name "OSC_EN") (class "Default")
      (node (ref "R11") (pin "1") (pinfunction "1_1") (pintype "input"))
      (node (ref "R8") (pin "2") (pinfunction "2_2") (pintype "input"))
      (node (ref "R9") (pin "2") (pinfunction "2_2") (pintype "input"))
      (node (ref "X1") (pin "1") (pinfunction "EN_1") (pintype "unspecified"))
    )
    (net (code "51") (name "PA14_SWCLK_BOOT0") (class "Default")
      (node (ref "R1") (pin "2") (pinfunction "2_2") (pintype "input"))
      (node (ref "R2") (pin "2") (pinfunction "2_2") (pintype "input"))
      (node (ref "TP4") (pin "1") (pinfunction "1_1") (pintype "input"))
      (node (ref "U1") (pin "25") (pinfunction "PA14-BOOT0_25") (pintype "unspecified"))
    )
    (net (code "52") (name "SYS_BOOT") (class "Default")
      (node (ref "J1") (pin "4") (pinfunction "4_4") (pintype "unspecified"))
      (node (ref "J8") (pin "4") (pinfunction "4_4") (pintype "unspecified"))
      (node (ref "R2") (pin "1") (pinfunction "1_1") (pintype "input"))
    )
    (net (code "53") (name "SYS_NRST") (class "Default")
      (node (ref "C3") (pin "2") (pinfunction "2_2") (pintype "unspecified"))
      (node (ref "J1") (pin "1") (pinfunction "1_1") (pintype "unspecified"))
      (node (ref "J8") (pin "1") (pinfunction "1_1") (pintype "unspecified"))
      (node (ref "R6") (pin "2") (pinfunction "2_2") (pintype "input"))
      (node (ref "TP5") (pin "1") (pinfunction "1_1") (pintype "input"))
      (node (ref "U1") (pin "6") (pinfunction "PF2-NRST_6") (pintype "unspecified"))
    )
    (net (code "54") (name "SYS_SWCLK") (class "Default")
      (node (ref "J1") (pin "3") (pinfunction "3_3") (pintype "unspecified"))
      (node (ref "J8") (pin "3") (pinfunction "3_3") (pintype "unspecified"))
      (node (ref "R1") (pin "1") (pinfunction "1_1") (pintype "input"))
    )
    (net (code "55") (name "SYS_SWDIO") (class "Default")
      (node (ref "J1") (pin "2") (pinfunction "2_2") (pintype "unspecified"))
      (node (ref "J8") (pin "2") (pinfunction "2_2") (pintype "unspecified"))
      (node (ref "TP3") (pin "1") (pinfunction "1_1") (pintype "input"))
      (node (ref "U1") (pin "24") (pinfunction "PA13_24") (pintype "unspecified"))
    )
    (net (code "56") (name "VDD_CORE") (class "Default")
      (node (ref "C1") (pin "2") (pinfunction "2_2") (pintype "unspecified"))
      (node (ref "C2") (pin "2") (pinfunction "2_2") (pintype "unspecified"))
      (node (ref "R5") (pin "1") (pinfunction "1_1") (pintype "input"))
      (node (ref "R6") (pin "1") (pinfunction "1_1") (pintype "input"))
      (node (ref "R7") (pin "2") (pinfunction "2_2") (pintype "input"))
      (node (ref "TP1") (pin "1") (pinfunction "1_1") (pintype "input"))
      (node (ref "U1") (pin "4") (pinfunction "VDD/VDDA_4") (pintype "unspecified"))
    )
    (net (code "57") (name "VDD_OSC") (class "Default")
      (node (ref "C4") (pin "2") (pinfunction "2_2") (pintype "unspecified"))
      (node (ref "R5") (pin "2") (pinfunction "2_2") (pintype "input"))
      (node (ref "R8") (pin "1") (pinfunction "1_1") (pintype "input"))
      (node (ref "X1") (pin "4") (pinfunction "VDD_4") (pintype "unspecified"))
    )
  )
)
